# extrudernode.net
KiCad netlist of a schematic drawn in EAGLE
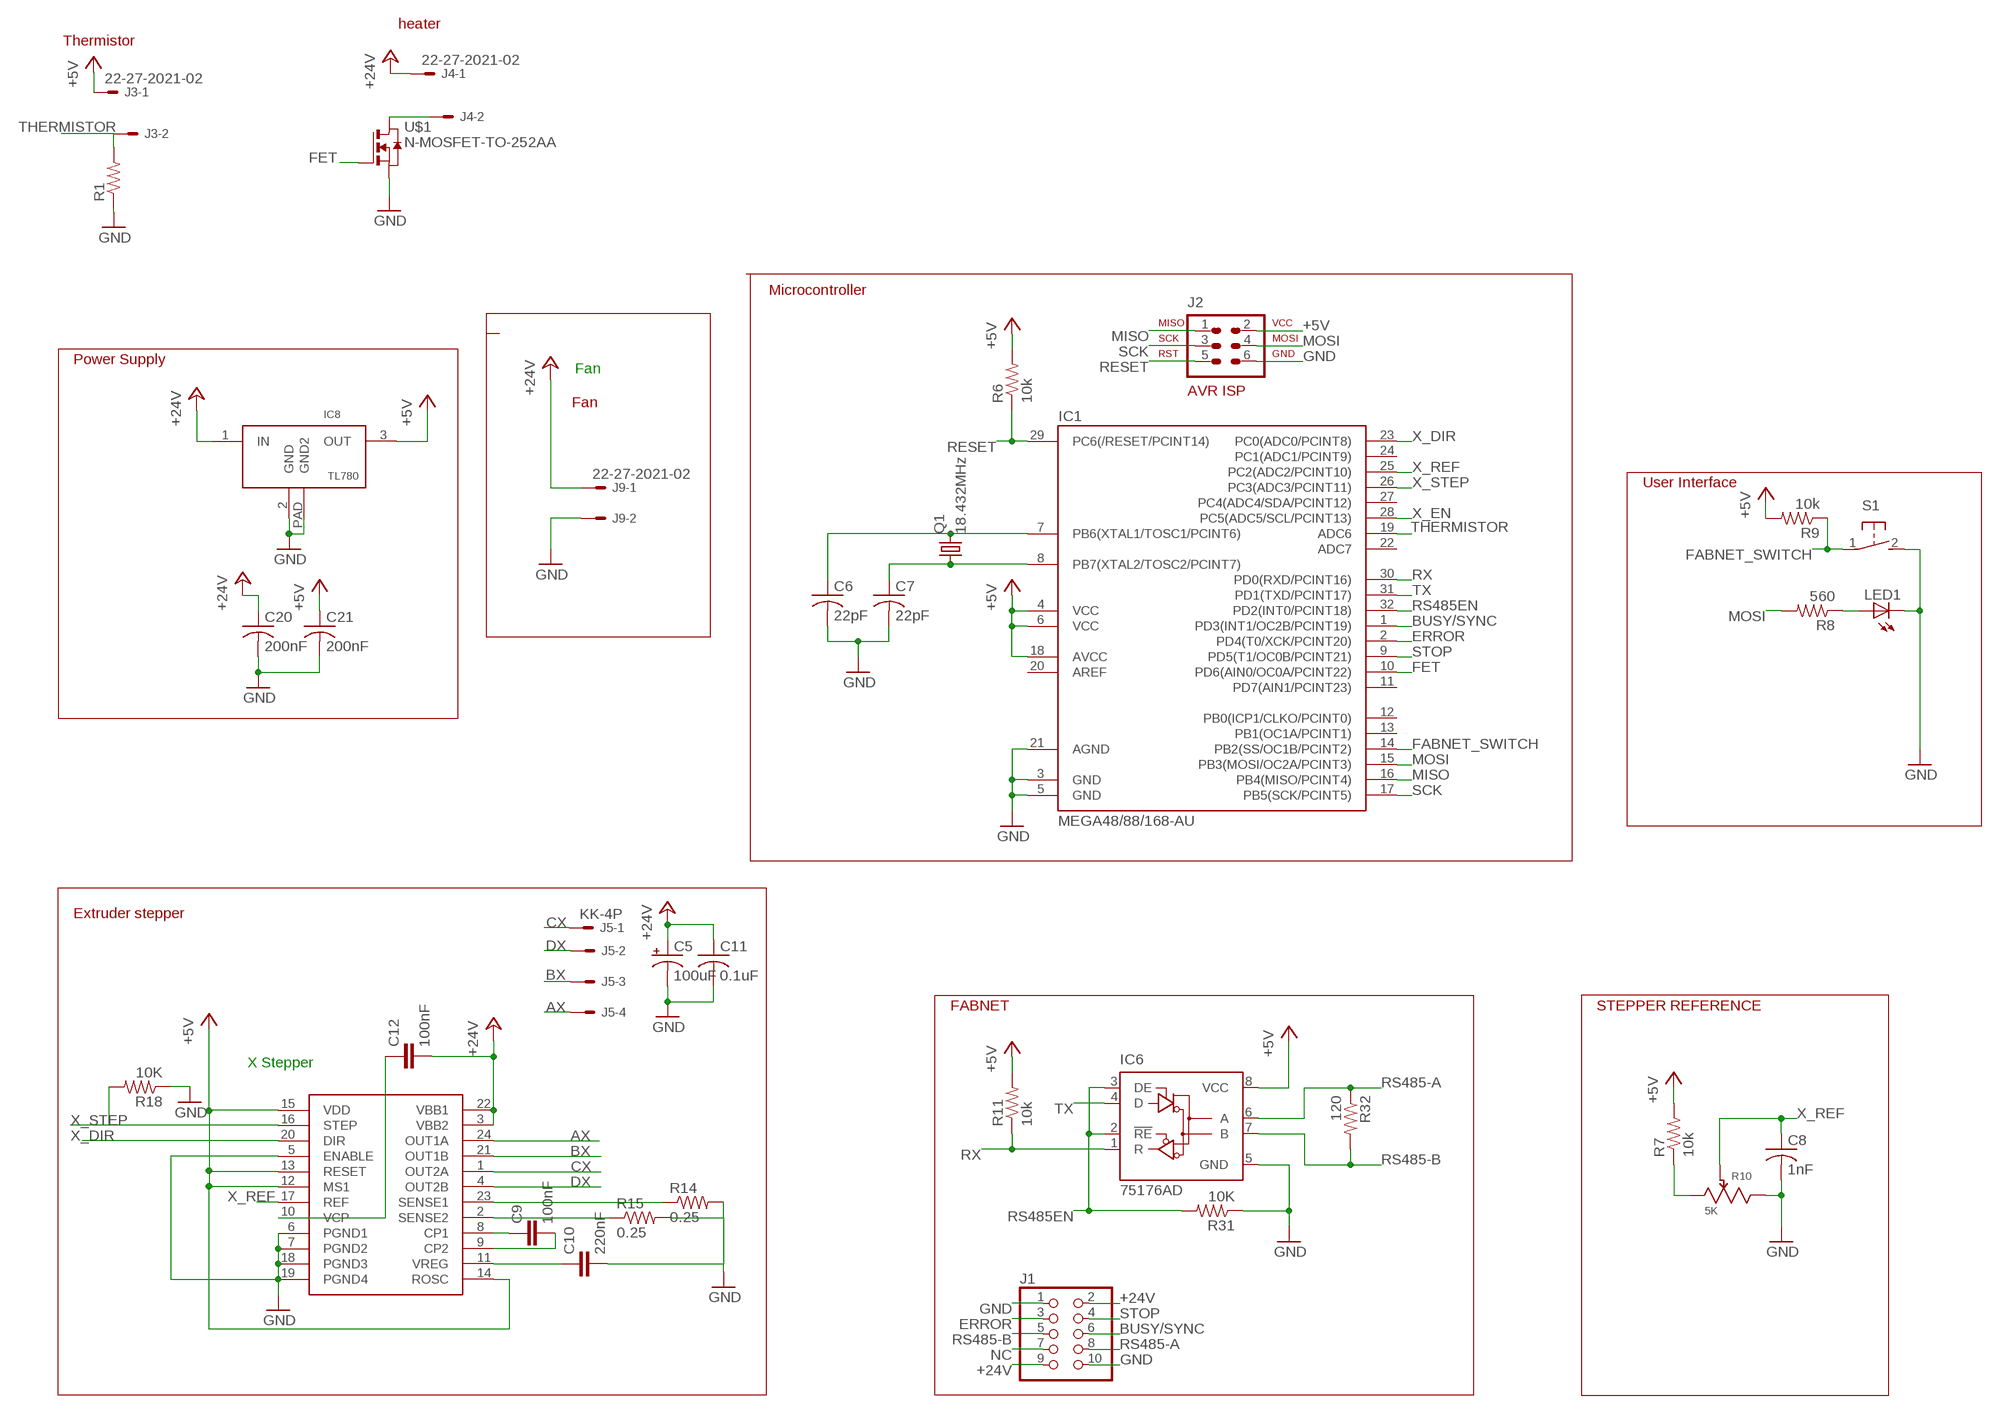
[diagram p0: schematic, sheet 1]

(export (version "E")
  (design (tool "Eeschema 10.0.6"))
  (components
    (comp (ref "C5")
      (value "100uF")
      (footprint "eagle-import:PANASONIC_D")
      (libsource (lib "eagle-import") (part "CPOL-USD"))
    )
    (comp (ref "C6")
      (value "22pF")
      (footprint "eagle-import:C0805@1")
      (libsource (lib "eagle-import") (part "C-USC0805"))
    )
    (comp (ref "C7")
      (value "22pF")
      (footprint "eagle-import:C0805@1")
      (libsource (lib "eagle-import") (part "C-USC0805"))
    )
    (comp (ref "C8")
      (value "1nF")
      (footprint "eagle-import:C0805@1")
      (libsource (lib "eagle-import") (part "C-USC0805"))
    )
    (comp (ref "C9")
      (value "100nF")
      (footprint "eagle-import:C1206")
      (libsource (lib "eagle-import") (part "C-EUC1206"))
    )
    (comp (ref "C10")
      (value "220nF")
      (footprint "eagle-import:C1206")
      (libsource (lib "eagle-import") (part "C-EUC1206"))
    )
    (comp (ref "C11")
      (value "0.1uF")
      (footprint "eagle-import:C0805@1")
      (libsource (lib "eagle-import") (part "C-USC0805"))
    )
    (comp (ref "C12")
      (value "100nF")
      (footprint "eagle-import:C1206")
      (libsource (lib "eagle-import") (part "C-EUC1206"))
    )
    (comp (ref "C20")
      (value "200nF")
      (footprint "eagle-import:C0805@1")
      (libsource (lib "eagle-import") (part "C-USC0805"))
    )
    (comp (ref "C21")
      (value "200nF")
      (footprint "eagle-import:C0805@1")
      (libsource (lib "eagle-import") (part "C-USC0805"))
    )
    (comp (ref "DRIVER3")
      (value "A3982")
      (footprint "eagle-import:SO24W")
      (libsource (lib "eagle-import") (part "A3982SOIC24"))
    )
    (comp (ref "IC1")
      (value "MEGA48/88/168-AU")
      (footprint "eagle-import:TQFP32-08")
      (libsource (lib "eagle-import") (part "MEGA48/88/168-AU"))
    )
    (comp (ref "IC6")
      (value "75176AD")
      (footprint "eagle-import:D_R-PDSO-G8")
      (libsource (lib "eagle-import") (part "75176AD"))
    )
    (comp (ref "IC8")
      (value "TL780_VREG")
      (footprint "eagle-import:D2PAK-3")
      (libsource (lib "eagle-import") (part "TL780_VREG"))
    )
    (comp (ref "J1")
      (value "PINHD-2X5")
      (footprint "eagle-import:2X05")
      (libsource (lib "eagle-import") (part "PINHD-2X5"))
    )
    (comp (ref "J2")
      (value "AVR-ISP-6VERT")
      (footprint "eagle-import:AVR-ISP-6")
      (libsource (lib "eagle-import") (part "AVR-ISP-6VERT"))
    )
    (comp (ref "J3")
      (value "22-27-2021-02")
      (footprint "eagle-import:6410-02")
      (libsource (lib "eagle-import") (part "22-?-0227-2021"))
    )
    (comp (ref "J4")
      (value "22-27-2021-02")
      (footprint "eagle-import:6410-02")
      (libsource (lib "eagle-import") (part "22-?-0227-2021"))
    )
    (comp (ref "J5")
      (value "KK-4P")
      (footprint "eagle-import:7395-04")
      (libsource (lib "eagle-import") (part "22-?-0405-7048"))
    )
    (comp (ref "J9")
      (value "22-27-2021-02")
      (footprint "eagle-import:6410-02")
      (libsource (lib "eagle-import") (part "22-?-0227-2021"))
    )
    (comp (ref "LED1")
      (value "LEDCHIPLED_0603")
      (footprint "eagle-import:CHIPLED_0603")
      (libsource (lib "eagle-import") (part "LEDCHIPLED_0603"))
    )
    (comp (ref "Q1")
      (value "18.432MHz")
      (footprint "eagle-import:HC49UP")
      (fields (field (name "OC_FARNELL") "unknown") (field (name "OC_NEWARK") "unknown"))
      (libsource (lib "eagle-import") (part "CRYSTALHC49UP"))
    )
    (comp (ref "R1")
      (value "RESISTOR1206")
      (footprint "eagle-import:1206")
      (libsource (lib "eagle-import") (part "RESISTOR1206"))
    )
    (comp (ref "R6")
      (value "10k")
      (footprint "eagle-import:R0805")
      (libsource (lib "eagle-import") (part "R-US_R0805"))
    )
    (comp (ref "R7")
      (value "10k")
      (footprint "eagle-import:R0805")
      (libsource (lib "eagle-import") (part "R-US_R0805"))
    )
    (comp (ref "R8")
      (value "560")
      (footprint "eagle-import:R0805")
      (libsource (lib "eagle-import") (part "R-US_R0805"))
    )
    (comp (ref "R9")
      (value "10k")
      (footprint "eagle-import:R0805")
      (libsource (lib "eagle-import") (part "R-US_R0805"))
    )
    (comp (ref "R10")
      (value "5K")
      (footprint "eagle-import:BOURN_TRIM")
      (libsource (lib "eagle-import") (part "BOURN_POT"))
    )
    (comp (ref "R11")
      (value "10k")
      (footprint "eagle-import:R0805")
      (libsource (lib "eagle-import") (part "R-US_R0805"))
    )
    (comp (ref "R14")
      (value "0.25")
      (footprint "eagle-import:R2512")
      (libsource (lib "eagle-import") (part "R-US_R2512"))
    )
    (comp (ref "R15")
      (value "0.25")
      (footprint "eagle-import:R2512")
      (libsource (lib "eagle-import") (part "R-US_R2512"))
    )
    (comp (ref "R18")
      (value "10K")
      (footprint "eagle-import:R1206")
      (libsource (lib "eagle-import") (part "resistor_R-US_R1206"))
    )
    (comp (ref "R31")
      (value "10K")
      (footprint "eagle-import:R0805")
      (libsource (lib "eagle-import") (part "R-US_R0805"))
    )
    (comp (ref "R32")
      (value "120")
      (footprint "eagle-import:R0805")
      (libsource (lib "eagle-import") (part "R-US_R0805"))
    )
    (comp (ref "S1")
      (value "31-XX")
      (footprint "eagle-import:B3F-31XX")
      (fields (field (name "MPN") "B3F-3100"))
      (libsource (lib "eagle-import") (part "31-XX"))
    )
    (comp (ref "U$1")
      (value "N-MOSFET-TO-252AA")
      (footprint "eagle-import:TO-252AA")
      (libsource (lib "eagle-import") (part "N-MOSFET-TO-252AA"))
    )
  )
  (nets
    (net (code "1") (name "+5V") (class "Default")
      (node (ref "C21") (pin "1") (pinfunction "1_1") (pintype "passive"))
      (node (ref "DRIVER3") (pin "12") (pinfunction "MS1_12") (pintype "bidirectional"))
      (node (ref "DRIVER3") (pin "13") (pinfunction "RESET_13") (pintype "bidirectional"))
      (node (ref "DRIVER3") (pin "14") (pinfunction "ROSC_14") (pintype "bidirectional"))
      (node (ref "DRIVER3") (pin "15") (pinfunction "VDD_15") (pintype "bidirectional"))
      (node (ref "IC1") (pin "18") (pinfunction "AVCC_18") (pintype "passive"))
      (node (ref "IC1") (pin "4") (pinfunction "VCC_4") (pintype "power_in"))
      (node (ref "IC1") (pin "6") (pinfunction "VCC_6") (pintype "power_in"))
      (node (ref "IC6") (pin "8") (pinfunction "VCC_8") (pintype "power_in"))
      (node (ref "IC8") (pin "3") (pinfunction "OUT_3") (pintype "bidirectional"))
      (node (ref "J2") (pin "2") (pinfunction "2_2") (pintype "passive"))
      (node (ref "J3") (pin "1") (pinfunction "S_1") (pintype "passive"))
      (node (ref "R11") (pin "2") (pinfunction "2_2") (pintype "passive"))
      (node (ref "R6") (pin "2") (pinfunction "2_2") (pintype "passive"))
      (node (ref "R7") (pin "2") (pinfunction "2_2") (pintype "passive"))
      (node (ref "R9") (pin "2") (pinfunction "2_2") (pintype "passive"))
    )
    (net (code "2") (name "+24V") (class "Default")
      (node (ref "C11") (pin "1") (pinfunction "1_1") (pintype "passive"))
      (node (ref "C12") (pin "2") (pinfunction "2_2") (pintype "passive"))
      (node (ref "C20") (pin "1") (pinfunction "1_1") (pintype "passive"))
      (node (ref "C5") (pin "+") (pinfunction "+_+") (pintype "passive"))
      (node (ref "DRIVER3") (pin "22") (pinfunction "VBB1_22") (pintype "bidirectional"))
      (node (ref "DRIVER3") (pin "3") (pinfunction "VBB2_3") (pintype "bidirectional"))
      (node (ref "IC8") (pin "1") (pinfunction "IN_1") (pintype "bidirectional"))
      (node (ref "J1") (pin "2") (pinfunction "2_2") (pintype "passive"))
      (node (ref "J1") (pin "9") (pinfunction "9_9") (pintype "passive"))
      (node (ref "J4") (pin "1") (pinfunction "S_1") (pintype "passive"))
      (node (ref "J9") (pin "1") (pinfunction "S_1") (pintype "passive"))
    )
    (net (code "3") (name "/AX") (class "Default")
      (node (ref "DRIVER3") (pin "24") (pinfunction "OUT1A_24") (pintype "bidirectional"))
      (node (ref "J5") (pin "4") (pinfunction "S_4") (pintype "passive"))
    )
    (net (code "4") (name "/BUSY{slash}SYNC") (class "Default")
      (node (ref "IC1") (pin "1") (pinfunction "PD3(INT1/OC2B/PCINT19)_1") (pintype "bidirectional"))
      (node (ref "J1") (pin "6") (pinfunction "6_6") (pintype "passive"))
    )
    (net (code "5") (name "/BX") (class "Default")
      (node (ref "DRIVER3") (pin "21") (pinfunction "OUT1B_21") (pintype "bidirectional"))
      (node (ref "J5") (pin "3") (pinfunction "S_3") (pintype "passive"))
    )
    (net (code "6") (name "/CX") (class "Default")
      (node (ref "DRIVER3") (pin "1") (pinfunction "OUT2A_1") (pintype "bidirectional"))
      (node (ref "J5") (pin "1") (pinfunction "S_1") (pintype "passive"))
    )
    (net (code "7") (name "/DX") (class "Default")
      (node (ref "DRIVER3") (pin "4") (pinfunction "OUT2B_4") (pintype "bidirectional"))
      (node (ref "J5") (pin "2") (pinfunction "S_2") (pintype "passive"))
    )
    (net (code "8") (name "/ERROR") (class "Default")
      (node (ref "IC1") (pin "2") (pinfunction "PD4(T0/XCK/PCINT20)_2") (pintype "bidirectional"))
      (node (ref "J1") (pin "3") (pinfunction "3_3") (pintype "passive"))
    )
    (net (code "9") (name "/FABNET_SWITCH") (class "Default")
      (node (ref "IC1") (pin "14") (pinfunction "PB2(SS/OC1B/PCINT2)_14") (pintype "bidirectional"))
      (node (ref "R9") (pin "1") (pinfunction "1_1") (pintype "passive"))
      (node (ref "S1") (pin "1") (pinfunction "P_1") (pintype "passive"))
    )
    (net (code "10") (name "/FET") (class "Default")
      (node (ref "IC1") (pin "10") (pinfunction "PD6(AIN0/OC0A/PCINT22)_10") (pintype "bidirectional"))
      (node (ref "U$1") (pin "GATE") (pinfunction "G_GATE") (pintype "passive"))
    )
    (net (code "11") (name "/MISO") (class "Default")
      (node (ref "IC1") (pin "16") (pinfunction "PB4(MISO/PCINT4)_16") (pintype "bidirectional"))
      (node (ref "J2") (pin "1") (pinfunction "1_1") (pintype "passive"))
    )
    (net (code "12") (name "/MOSI") (class "Default")
      (node (ref "IC1") (pin "15") (pinfunction "PB3(MOSI/OC2A/PCINT3)_15") (pintype "bidirectional"))
      (node (ref "J2") (pin "4") (pinfunction "4_4") (pintype "passive"))
      (node (ref "R8") (pin "2") (pinfunction "2_2") (pintype "passive"))
    )
    (net (code "13") (name "/NC") (class "Default")
      (node (ref "J1") (pin "7") (pinfunction "7_7") (pintype "passive"))
    )
    (net (code "14") (name "/RESET") (class "Default")
      (node (ref "IC1") (pin "29") (pinfunction "PC6(/RESET/PCINT14)_29") (pintype "bidirectional"))
      (node (ref "J2") (pin "5") (pinfunction "5_5") (pintype "passive"))
      (node (ref "R6") (pin "1") (pinfunction "1_1") (pintype "passive"))
    )
    (net (code "15") (name "/RS485-A") (class "Default")
      (node (ref "IC6") (pin "6") (pinfunction "A_6") (pintype "output"))
      (node (ref "J1") (pin "8") (pinfunction "8_8") (pintype "passive"))
      (node (ref "R32") (pin "1") (pinfunction "1_1") (pintype "passive"))
    )
    (net (code "16") (name "/RS485-B") (class "Default")
      (node (ref "IC6") (pin "7") (pinfunction "B_7") (pintype "output"))
      (node (ref "J1") (pin "5") (pinfunction "5_5") (pintype "passive"))
      (node (ref "R32") (pin "2") (pinfunction "2_2") (pintype "passive"))
    )
    (net (code "17") (name "/RS485EN") (class "Default")
      (node (ref "IC1") (pin "32") (pinfunction "PD2(INT0/PCINT18)_32") (pintype "bidirectional"))
      (node (ref "IC6") (pin "2") (pinfunction "~{RE}_2") (pintype "input"))
      (node (ref "IC6") (pin "3") (pinfunction "DE_3") (pintype "input"))
      (node (ref "R31") (pin "2") (pinfunction "2_2") (pintype "passive"))
    )
    (net (code "18") (name "/RX") (class "Default")
      (node (ref "IC1") (pin "30") (pinfunction "PD0(RXD/PCINT16)_30") (pintype "bidirectional"))
      (node (ref "IC6") (pin "1") (pinfunction "R_1") (pintype "input"))
      (node (ref "R11") (pin "1") (pinfunction "1_1") (pintype "passive"))
    )
    (net (code "19") (name "/SCK") (class "Default")
      (node (ref "IC1") (pin "17") (pinfunction "PB5(SCK/PCINT5)_17") (pintype "bidirectional"))
      (node (ref "J2") (pin "3") (pinfunction "3_3") (pintype "passive"))
    )
    (net (code "20") (name "/STOP") (class "Default")
      (node (ref "IC1") (pin "9") (pinfunction "PD5(T1/OC0B/PCINT21)_9") (pintype "bidirectional"))
      (node (ref "J1") (pin "4") (pinfunction "4_4") (pintype "passive"))
    )
    (net (code "21") (name "/THERMISTOR") (class "Default")
      (node (ref "IC1") (pin "19") (pinfunction "ADC6_19") (pintype "passive"))
      (node (ref "J3") (pin "2") (pinfunction "S_2") (pintype "passive"))
      (node (ref "R1") (pin "2") (pinfunction "2_2") (pintype "passive"))
    )
    (net (code "22") (name "/TX") (class "Default")
      (node (ref "IC1") (pin "31") (pinfunction "PD1(TXD/PCINT17)_31") (pintype "bidirectional"))
      (node (ref "IC6") (pin "4") (pinfunction "D_4") (pintype "input"))
    )
    (net (code "23") (name "/X_DIR") (class "Default")
      (node (ref "DRIVER3") (pin "20") (pinfunction "DIR_20") (pintype "bidirectional"))
      (node (ref "IC1") (pin "23") (pinfunction "PC0(ADC0/PCINT8)_23") (pintype "bidirectional"))
    )
    (net (code "24") (name "/X_EN") (class "Default")
      (node (ref "IC1") (pin "28") (pinfunction "PC5(ADC5/SCL/PCINT13)_28") (pintype "bidirectional"))
    )
    (net (code "25") (name "/X_REF") (class "Default")
      (node (ref "C8") (pin "1") (pinfunction "1_1") (pintype "passive"))
      (node (ref "DRIVER3") (pin "17") (pinfunction "REF_17") (pintype "bidirectional"))
      (node (ref "IC1") (pin "25") (pinfunction "PC2(ADC2/PCINT10)_25") (pintype "bidirectional"))
      (node (ref "R10") (pin "2") (pinfunction "2_2") (pintype "bidirectional"))
    )
    (net (code "26") (name "/X_STEP") (class "Default")
      (node (ref "DRIVER3") (pin "16") (pinfunction "STEP_16") (pintype "bidirectional"))
      (node (ref "IC1") (pin "26") (pinfunction "PC3(ADC3/PCINT11)_26") (pintype "bidirectional"))
      (node (ref "R18") (pin "2") (pinfunction "2_2") (pintype "passive"))
    )
    (net (code "27") (name "GND") (class "Default")
      (node (ref "C10") (pin "2") (pinfunction "2_2") (pintype "passive"))
      (node (ref "C11") (pin "2") (pinfunction "2_2") (pintype "passive"))
      (node (ref "C20") (pin "2") (pinfunction "2_2") (pintype "passive"))
      (node (ref "C21") (pin "2") (pinfunction "2_2") (pintype "passive"))
      (node (ref "C5") (pin "-") (pinfunction "-_-") (pintype "passive"))
      (node (ref "C6") (pin "2") (pinfunction "2_2") (pintype "passive"))
      (node (ref "C7") (pin "2") (pinfunction "2_2") (pintype "passive"))
      (node (ref "C8") (pin "2") (pinfunction "2_2") (pintype "passive"))
      (node (ref "DRIVER3") (pin "18") (pinfunction "PGND3_18") (pintype "bidirectional"))
      (node (ref "DRIVER3") (pin "19") (pinfunction "PGND4_19") (pintype "bidirectional"))
      (node (ref "DRIVER3") (pin "5") (pinfunction "ENABLE_5") (pintype "bidirectional"))
      (node (ref "DRIVER3") (pin "6") (pinfunction "PGND1_6") (pintype "bidirectional"))
      (node (ref "DRIVER3") (pin "7") (pinfunction "PGND2_7") (pintype "bidirectional"))
      (node (ref "IC1") (pin "21") (pinfunction "AGND_21") (pintype "power_in"))
      (node (ref "IC1") (pin "3") (pinfunction "GND_3") (pintype "power_in"))
      (node (ref "IC1") (pin "5") (pinfunction "GND_5") (pintype "power_in"))
      (node (ref "IC6") (pin "5") (pinfunction "GND_5") (pintype "power_in"))
      (node (ref "IC8") (pin "2") (pinfunction "GND_2") (pintype "bidirectional"))
      (node (ref "IC8") (pin "PAD") (pinfunction "GND2_PAD") (pintype "bidirectional"))
      (node (ref "J1") (pin "1") (pinfunction "1_1") (pintype "passive"))
      (node (ref "J1") (pin "10") (pinfunction "10_10") (pintype "passive"))
      (node (ref "J2") (pin "6") (pinfunction "6_6") (pintype "passive"))
      (node (ref "J9") (pin "2") (pinfunction "S_2") (pintype "passive"))
      (node (ref "LED1") (pin "C") (pinfunction "C_C") (pintype "passive"))
      (node (ref "R1") (pin "1") (pinfunction "1_1") (pintype "passive"))
      (node (ref "R10") (pin "3") (pinfunction "3_3") (pintype "bidirectional"))
      (node (ref "R14") (pin "2") (pinfunction "2_2") (pintype "passive"))
      (node (ref "R15") (pin "2") (pinfunction "2_2") (pintype "passive"))
      (node (ref "R18") (pin "1") (pinfunction "1_1") (pintype "passive"))
      (node (ref "R31") (pin "1") (pinfunction "1_1") (pintype "passive"))
      (node (ref "S1") (pin "2") (pinfunction "S_2") (pintype "passive"))
      (node (ref "U$1") (pin "SOURCE") (pinfunction "S_SOURCE") (pintype "passive"))
    )
    (net (code "28") (name "Net-(DRIVER3-CP1)") (class "Default")
      (node (ref "C9") (pin "1") (pinfunction "1_1") (pintype "passive"))
      (node (ref "DRIVER3") (pin "8") (pinfunction "CP1_8") (pintype "bidirectional"))
    )
    (net (code "29") (name "Net-(DRIVER3-CP2)") (class "Default")
      (node (ref "C9") (pin "2") (pinfunction "2_2") (pintype "passive"))
      (node (ref "DRIVER3") (pin "9") (pinfunction "CP2_9") (pintype "bidirectional"))
    )
    (net (code "30") (name "Net-(DRIVER3-SENSE1)") (class "Default")
      (node (ref "DRIVER3") (pin "23") (pinfunction "SENSE1_23") (pintype "bidirectional"))
      (node (ref "R14") (pin "1") (pinfunction "1_1") (pintype "passive"))
    )
    (net (code "31") (name "Net-(DRIVER3-SENSE2)") (class "Default")
      (node (ref "DRIVER3") (pin "2") (pinfunction "SENSE2_2") (pintype "bidirectional"))
      (node (ref "R15") (pin "1") (pinfunction "1_1") (pintype "passive"))
    )
    (net (code "32") (name "Net-(DRIVER3-VCP)") (class "Default")
      (node (ref "C12") (pin "1") (pinfunction "1_1") (pintype "passive"))
      (node (ref "DRIVER3") (pin "10") (pinfunction "VCP_10") (pintype "bidirectional"))
    )
    (net (code "33") (name "Net-(DRIVER3-VREG)") (class "Default")
      (node (ref "C10") (pin "1") (pinfunction "1_1") (pintype "passive"))
      (node (ref "DRIVER3") (pin "11") (pinfunction "VREG_11") (pintype "bidirectional"))
    )
    (net (code "34") (name "Net-(IC1-PB6(XTAL1{slash}TOSC1{slash}PCINT6))") (class "Default")
      (node (ref "C6") (pin "1") (pinfunction "1_1") (pintype "passive"))
      (node (ref "IC1") (pin "7") (pinfunction "PB6(XTAL1/TOSC1/PCINT6)_7") (pintype "bidirectional"))
      (node (ref "Q1") (pin "2") (pinfunction "2_2") (pintype "passive"))
    )
    (net (code "35") (name "Net-(IC1-PB7(XTAL2{slash}TOSC2{slash}PCINT7))") (class "Default")
      (node (ref "C7") (pin "1") (pinfunction "1_1") (pintype "passive"))
      (node (ref "IC1") (pin "8") (pinfunction "PB7(XTAL2/TOSC2/PCINT7)_8") (pintype "bidirectional"))
      (node (ref "Q1") (pin "1") (pinfunction "1_1") (pintype "passive"))
    )
    (net (code "36") (name "Net-(J4B-S)") (class "Default")
      (node (ref "J4") (pin "2") (pinfunction "S_2") (pintype "passive"))
      (node (ref "U$1") (pin "DRAIN") (pinfunction "D_DRAIN") (pintype "passive"))
    )
    (net (code "37") (name "Net-(LED1-PadA)") (class "Default")
      (node (ref "LED1") (pin "A") (pinfunction "A_A") (pintype "passive"))
      (node (ref "R8") (pin "1") (pinfunction "1_1") (pintype "passive"))
    )
    (net (code "38") (name "Net-(R10-Pad1)") (class "Default")
      (node (ref "R10") (pin "1") (pinfunction "1_1") (pintype "bidirectional"))
      (node (ref "R7") (pin "1") (pinfunction "1_1") (pintype "passive"))
    )
    (net (code "39") (name "unconnected-(IC1-ADC7-Pad22)") (class "Default")
      (node (ref "IC1") (pin "22") (pinfunction "ADC7_22") (pintype "passive"))
    )
    (net (code "40") (name "unconnected-(IC1-AREF-Pad20)") (class "Default")
      (node (ref "IC1") (pin "20") (pinfunction "AREF_20") (pintype "passive"))
    )
    (net (code "41") (name "unconnected-(IC1-PB0(ICP1{slash}CLKO{slash}PCINT0)-Pad12)") (class "Default")
      (node (ref "IC1") (pin "12") (pinfunction "PB0(ICP1/CLKO/PCINT0)_12") (pintype "bidirectional"))
    )
    (net (code "42") (name "unconnected-(IC1-PB1(OC1A{slash}PCINT1)-Pad13)") (class "Default")
      (node (ref "IC1") (pin "13") (pinfunction "PB1(OC1A/PCINT1)_13") (pintype "bidirectional"))
    )
    (net (code "43") (name "unconnected-(IC1-PC1(ADC1{slash}PCINT9)-Pad24)") (class "Default")
      (node (ref "IC1") (pin "24") (pinfunction "PC1(ADC1/PCINT9)_24") (pintype "bidirectional"))
    )
    (net (code "44") (name "unconnected-(IC1-PC4(ADC4{slash}SDA{slash}PCINT12)-Pad27)") (class "Default")
      (node (ref "IC1") (pin "27") (pinfunction "PC4(ADC4/SDA/PCINT12)_27") (pintype "bidirectional"))
    )
    (net (code "45") (name "unconnected-(IC1-PD7(AIN1{slash}PCINT23)-Pad11)") (class "Default")
      (node (ref "IC1") (pin "11") (pinfunction "PD7(AIN1/PCINT23)_11") (pintype "bidirectional"))
    )
  )
)
